# ASD2831.net
KiCad netlist of a schematic drawn in EAGLE
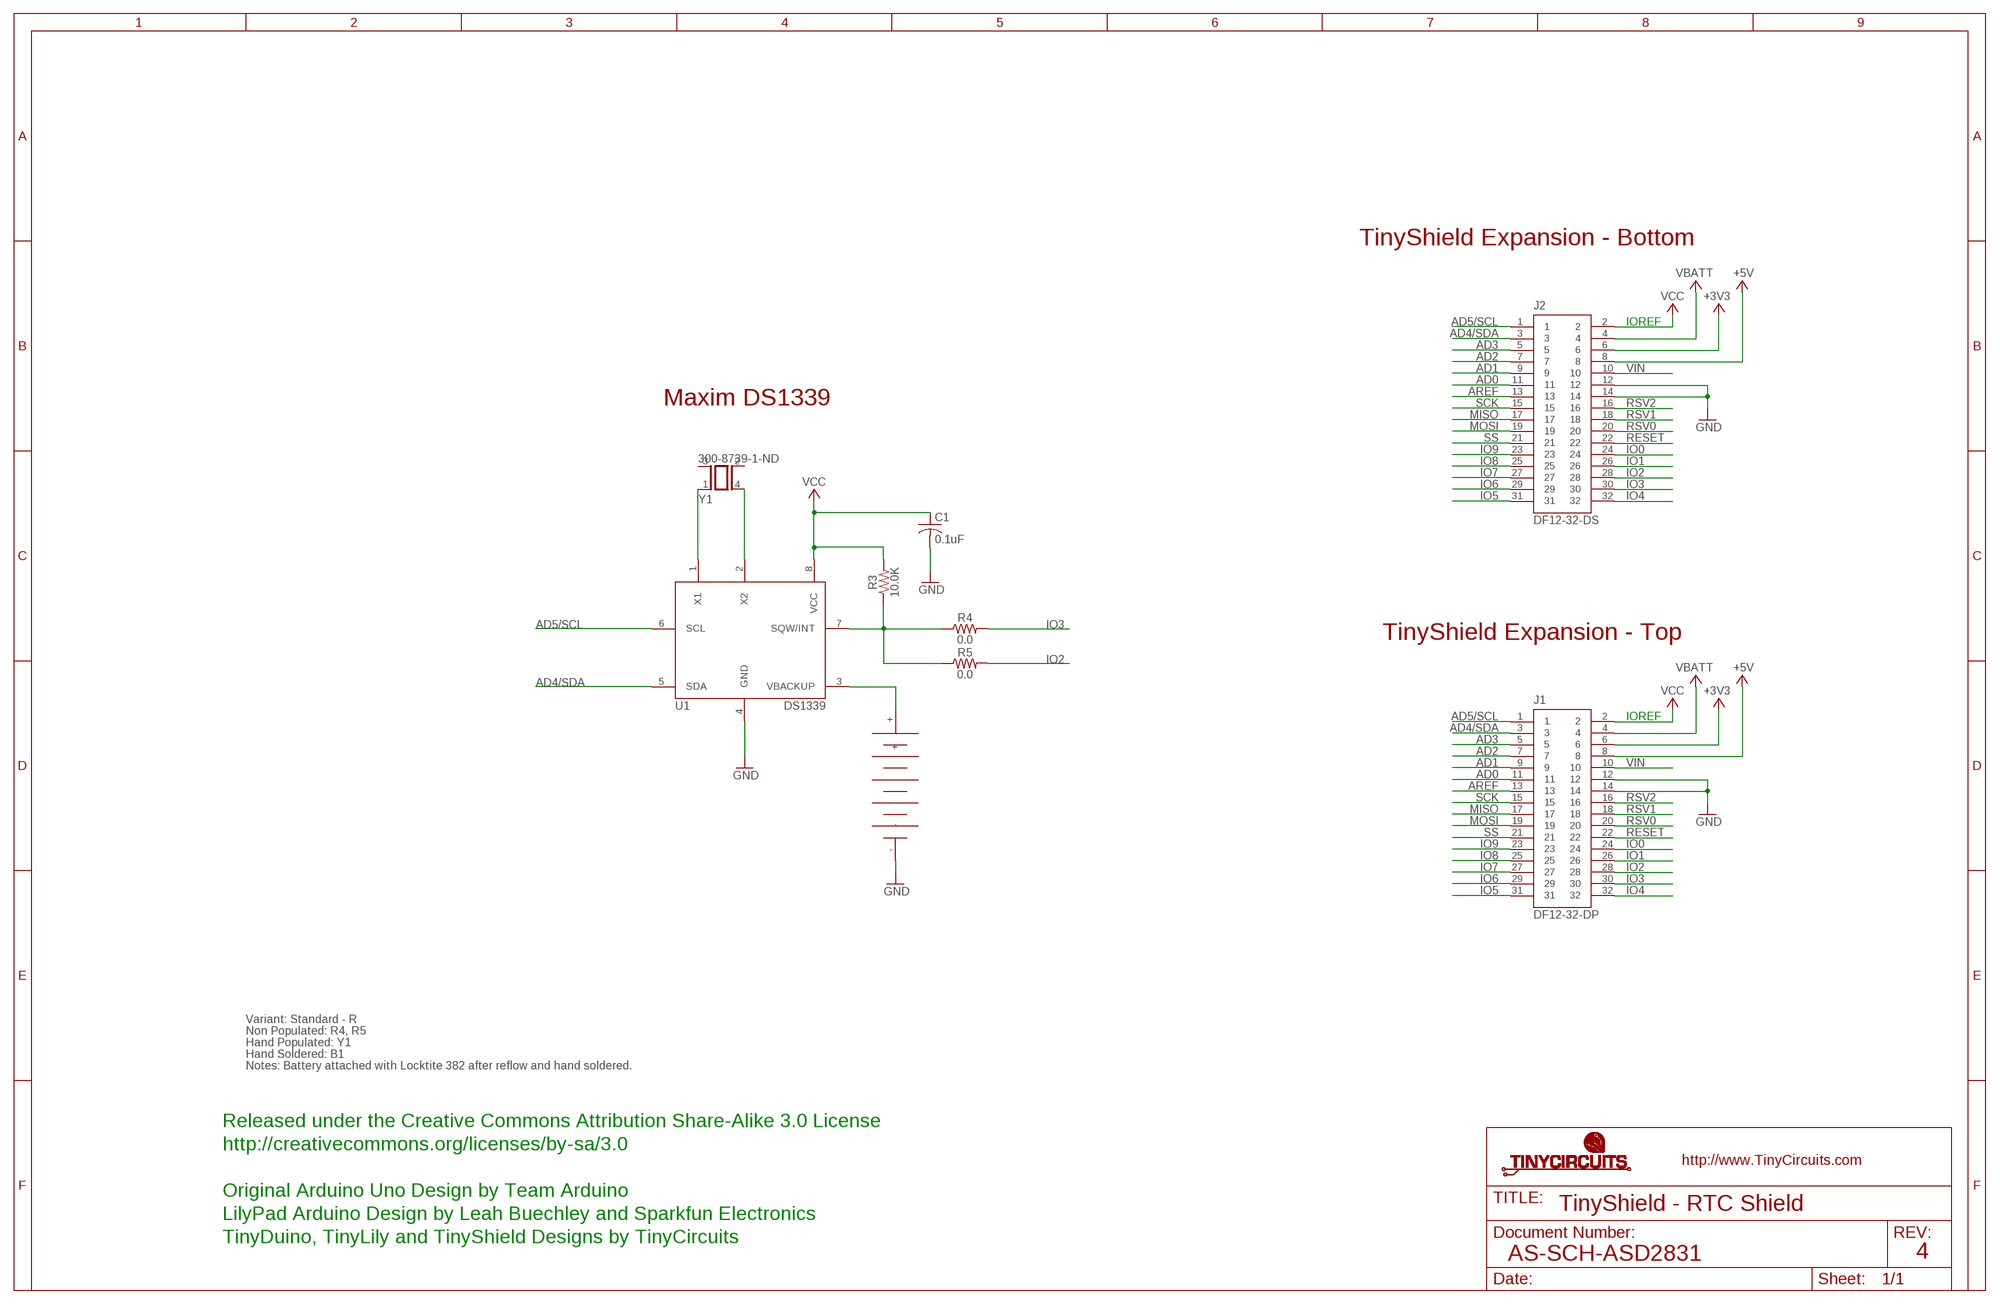
[diagram p0: schematic, sheet 1]

(export (version "E")
  (design (tool "Eeschema 10.0.6"))
  (components
    (comp (ref "B1")
      (value "ML-920S/DN")
      (footprint "eagle-import:ML-920S_DN")
      (fields (field (name "PARTNO") "AS-ITM-00182"))
      (libsource (lib "eagle-import") (part "AS-ITM-00182"))
    )
    (comp (ref "C1")
      (value "0.1uF")
      (footprint "eagle-import:C0402")
      (fields (field (name "PARTNO") "AS-ITM-00008"))
      (libsource (lib "eagle-import") (part "AS-ITM-00008"))
    )
    (comp (ref "J1")
      (value "DF12-32-DP")
      (footprint "eagle-import:DF12-32-DP")
      (fields (field (name "PARTNO") "AS-ITM-00015") (field (name "PARTNO_1") "AS-ITM-00015"))
      (libsource (lib "eagle-import") (part "AS-ITM-00015"))
    )
    (comp (ref "J2")
      (value "DF12-32-DS")
      (footprint "eagle-import:DF12-32-DS")
      (fields (field (name "PARTNO") "AS-ITM-00012") (field (name "PARTNO_1") "AS-ITM-00012"))
      (libsource (lib "eagle-import") (part "AS-ITM-00012"))
    )
    (comp (ref "R3")
      (value "10.0K")
      (footprint "eagle-import:0402")
      (fields (field (name "PARTNO") "AS-ITM-00032") (field (name "PARTNO_1") "AS-ITM-00032"))
      (libsource (lib "eagle-import") (part "AS-ITM-00032"))
    )
    (comp (ref "R4")
      (value "0.0")
      (footprint "eagle-import:0402_SHORT")
      (fields (field (name "PARTNO") "AS-ITM-00076"))
      (libsource (lib "eagle-import") (part "AS-ITM-000760402_SHORT"))
    )
    (comp (ref "R5")
      (value "0.0")
      (footprint "eagle-import:0402")
      (fields (field (name "PARTNO") "AS-ITM-00076"))
      (libsource (lib "eagle-import") (part "AS-ITM-00076"))
    )
    (comp (ref "U1")
      (value "DS1339")
      (footprint "eagle-import:8-USOP")
      (fields (field (name "PARTNO") "AS-ITM-00181"))
      (libsource (lib "eagle-import") (part "AS-ITM-00181"))
    )
    (comp (ref "Y1")
      (value "300-8739-1-ND")
      (footprint "eagle-import:CM200C-32.768KDZBT")
      (fields (field (name "PARTNO") "AS-ITM-00183"))
      (libsource (lib "eagle-import") (part "AS-ITM-00183"))
    )
  )
  (nets
    (net (code "1") (name "+3V3") (class "Default")
      (node (ref "J1") (pin "6") (pinfunction "6_6") (pintype "bidirectional"))
      (node (ref "J2") (pin "6") (pinfunction "6_6") (pintype "bidirectional"))
    )
    (net (code "2") (name "+5V") (class "Default")
      (node (ref "J1") (pin "8") (pinfunction "8_8") (pintype "bidirectional"))
      (node (ref "J2") (pin "8") (pinfunction "8_8") (pintype "bidirectional"))
    )
    (net (code "3") (name "/AD0") (class "Default")
      (node (ref "J1") (pin "11") (pinfunction "11_11") (pintype "bidirectional"))
      (node (ref "J2") (pin "11") (pinfunction "11_11") (pintype "bidirectional"))
    )
    (net (code "4") (name "/AD1") (class "Default")
      (node (ref "J1") (pin "9") (pinfunction "9_9") (pintype "bidirectional"))
      (node (ref "J2") (pin "9") (pinfunction "9_9") (pintype "bidirectional"))
    )
    (net (code "5") (name "/AD2") (class "Default")
      (node (ref "J1") (pin "7") (pinfunction "7_7") (pintype "bidirectional"))
      (node (ref "J2") (pin "7") (pinfunction "7_7") (pintype "bidirectional"))
    )
    (net (code "6") (name "/AD3") (class "Default")
      (node (ref "J1") (pin "5") (pinfunction "5_5") (pintype "bidirectional"))
      (node (ref "J2") (pin "5") (pinfunction "5_5") (pintype "bidirectional"))
    )
    (net (code "7") (name "/AD4{slash}SDA") (class "Default")
      (node (ref "J1") (pin "3") (pinfunction "3_3") (pintype "bidirectional"))
      (node (ref "J2") (pin "3") (pinfunction "3_3") (pintype "bidirectional"))
      (node (ref "U1") (pin "5") (pinfunction "SDA_5") (pintype "bidirectional"))
    )
    (net (code "8") (name "/AD5{slash}SCL") (class "Default")
      (node (ref "J1") (pin "1") (pinfunction "1_1") (pintype "bidirectional"))
      (node (ref "J2") (pin "1") (pinfunction "1_1") (pintype "bidirectional"))
      (node (ref "U1") (pin "6") (pinfunction "SCL_6") (pintype "bidirectional"))
    )
    (net (code "9") (name "/AREF") (class "Default")
      (node (ref "J1") (pin "13") (pinfunction "13_13") (pintype "bidirectional"))
      (node (ref "J2") (pin "13") (pinfunction "13_13") (pintype "bidirectional"))
    )
    (net (code "10") (name "/IO0") (class "Default")
      (node (ref "J1") (pin "24") (pinfunction "24_24") (pintype "bidirectional"))
      (node (ref "J2") (pin "24") (pinfunction "24_24") (pintype "bidirectional"))
    )
    (net (code "11") (name "/IO1") (class "Default")
      (node (ref "J1") (pin "26") (pinfunction "26_26") (pintype "bidirectional"))
      (node (ref "J2") (pin "26") (pinfunction "26_26") (pintype "bidirectional"))
    )
    (net (code "12") (name "/IO2") (class "Default")
      (node (ref "J1") (pin "28") (pinfunction "28_28") (pintype "bidirectional"))
      (node (ref "J2") (pin "28") (pinfunction "28_28") (pintype "bidirectional"))
      (node (ref "R5") (pin "2") (pinfunction "2_2") (pintype "passive"))
    )
    (net (code "13") (name "/IO3") (class "Default")
      (node (ref "J1") (pin "30") (pinfunction "30_30") (pintype "bidirectional"))
      (node (ref "J2") (pin "30") (pinfunction "30_30") (pintype "bidirectional"))
      (node (ref "R4") (pin "2") (pinfunction "2_2") (pintype "passive"))
    )
    (net (code "14") (name "/IO4") (class "Default")
      (node (ref "J1") (pin "32") (pinfunction "32_32") (pintype "bidirectional"))
      (node (ref "J2") (pin "32") (pinfunction "32_32") (pintype "bidirectional"))
    )
    (net (code "15") (name "/IO5") (class "Default")
      (node (ref "J1") (pin "31") (pinfunction "31_31") (pintype "bidirectional"))
      (node (ref "J2") (pin "31") (pinfunction "31_31") (pintype "bidirectional"))
    )
    (net (code "16") (name "/IO6") (class "Default")
      (node (ref "J1") (pin "29") (pinfunction "29_29") (pintype "bidirectional"))
      (node (ref "J2") (pin "29") (pinfunction "29_29") (pintype "bidirectional"))
    )
    (net (code "17") (name "/IO7") (class "Default")
      (node (ref "J1") (pin "27") (pinfunction "27_27") (pintype "bidirectional"))
      (node (ref "J2") (pin "27") (pinfunction "27_27") (pintype "bidirectional"))
    )
    (net (code "18") (name "/IO8") (class "Default")
      (node (ref "J1") (pin "25") (pinfunction "25_25") (pintype "bidirectional"))
      (node (ref "J2") (pin "25") (pinfunction "25_25") (pintype "bidirectional"))
    )
    (net (code "19") (name "/IO9") (class "Default")
      (node (ref "J1") (pin "23") (pinfunction "23_23") (pintype "bidirectional"))
      (node (ref "J2") (pin "23") (pinfunction "23_23") (pintype "bidirectional"))
    )
    (net (code "20") (name "/MISO") (class "Default")
      (node (ref "J1") (pin "17") (pinfunction "17_17") (pintype "bidirectional"))
      (node (ref "J2") (pin "17") (pinfunction "17_17") (pintype "bidirectional"))
    )
    (net (code "21") (name "/MOSI") (class "Default")
      (node (ref "J1") (pin "19") (pinfunction "19_19") (pintype "bidirectional"))
      (node (ref "J2") (pin "19") (pinfunction "19_19") (pintype "bidirectional"))
    )
    (net (code "22") (name "/RESET") (class "Default")
      (node (ref "J1") (pin "22") (pinfunction "22_22") (pintype "bidirectional"))
      (node (ref "J2") (pin "22") (pinfunction "22_22") (pintype "bidirectional"))
    )
    (net (code "23") (name "/RSV0") (class "Default")
      (node (ref "J1") (pin "20") (pinfunction "20_20") (pintype "bidirectional"))
      (node (ref "J2") (pin "20") (pinfunction "20_20") (pintype "bidirectional"))
    )
    (net (code "24") (name "/RSV1") (class "Default")
      (node (ref "J1") (pin "18") (pinfunction "18_18") (pintype "bidirectional"))
      (node (ref "J2") (pin "18") (pinfunction "18_18") (pintype "bidirectional"))
    )
    (net (code "25") (name "/RSV2") (class "Default")
      (node (ref "J1") (pin "16") (pinfunction "16_16") (pintype "bidirectional"))
      (node (ref "J2") (pin "16") (pinfunction "16_16") (pintype "bidirectional"))
    )
    (net (code "26") (name "/SCK") (class "Default")
      (node (ref "J1") (pin "15") (pinfunction "15_15") (pintype "bidirectional"))
      (node (ref "J2") (pin "15") (pinfunction "15_15") (pintype "bidirectional"))
    )
    (net (code "27") (name "/SS") (class "Default")
      (node (ref "J1") (pin "21") (pinfunction "21_21") (pintype "bidirectional"))
      (node (ref "J2") (pin "21") (pinfunction "21_21") (pintype "bidirectional"))
    )
    (net (code "28") (name "/VIN") (class "Default")
      (node (ref "J1") (pin "10") (pinfunction "10_10") (pintype "bidirectional"))
      (node (ref "J2") (pin "10") (pinfunction "10_10") (pintype "bidirectional"))
    )
    (net (code "29") (name "GND") (class "Default")
      (node (ref "B1") (pin "-") (pinfunction "-_-") (pintype "bidirectional"))
      (node (ref "C1") (pin "2") (pinfunction "2_2") (pintype "passive"))
      (node (ref "J1") (pin "12") (pinfunction "12_12") (pintype "bidirectional"))
      (node (ref "J1") (pin "14") (pinfunction "14_14") (pintype "bidirectional"))
      (node (ref "J2") (pin "12") (pinfunction "12_12") (pintype "bidirectional"))
      (node (ref "J2") (pin "14") (pinfunction "14_14") (pintype "bidirectional"))
      (node (ref "U1") (pin "4") (pinfunction "GND_4") (pintype "bidirectional"))
    )
    (net (code "30") (name "Net-(U1-SQW{slash}INT)") (class "Default")
      (node (ref "R3") (pin "1") (pinfunction "1_1") (pintype "passive"))
      (node (ref "R4") (pin "1") (pinfunction "1_1") (pintype "passive"))
      (node (ref "R5") (pin "1") (pinfunction "1_1") (pintype "passive"))
      (node (ref "U1") (pin "7") (pinfunction "SQW/INT_7") (pintype "bidirectional"))
    )
    (net (code "31") (name "Net-(U1-VBACKUP)") (class "Default")
      (node (ref "B1") (pin "+") (pinfunction "+_+") (pintype "bidirectional"))
      (node (ref "U1") (pin "3") (pinfunction "VBACKUP_3") (pintype "bidirectional"))
    )
    (net (code "32") (name "Net-(U1-X1)") (class "Default")
      (node (ref "U1") (pin "1") (pinfunction "X1_1") (pintype "bidirectional"))
      (node (ref "Y1") (pin "1") (pinfunction "1_1") (pintype "passive"))
    )
    (net (code "33") (name "Net-(U1-X2)") (class "Default")
      (node (ref "U1") (pin "2") (pinfunction "X2_2") (pintype "bidirectional"))
      (node (ref "Y1") (pin "4") (pinfunction "2_4") (pintype "passive"))
    )
    (net (code "34") (name "VBATT") (class "Default")
      (node (ref "J1") (pin "4") (pinfunction "4_4") (pintype "bidirectional"))
      (node (ref "J2") (pin "4") (pinfunction "4_4") (pintype "bidirectional"))
    )
    (net (code "35") (name "VCC") (class "Default")
      (node (ref "C1") (pin "1") (pinfunction "1_1") (pintype "passive"))
      (node (ref "J1") (pin "2") (pinfunction "2_2") (pintype "bidirectional"))
      (node (ref "J2") (pin "2") (pinfunction "2_2") (pintype "bidirectional"))
      (node (ref "R3") (pin "2") (pinfunction "2_2") (pintype "passive"))
      (node (ref "U1") (pin "8") (pinfunction "VCC_8") (pintype "bidirectional"))
    )
    (net (code "36") (name "unconnected-(Y1-3-Pad2)") (class "Default")
      (node (ref "Y1") (pin "2") (pinfunction "3_2") (pintype "passive"))
    )
    (net (code "37") (name "unconnected-(Y1-4-Pad3)") (class "Default")
      (node (ref "Y1") (pin "3") (pinfunction "4_3") (pintype "passive"))
    )
  )
)
